# Industrial-Controller_ESP8266.net
KiCad netlist of a schematic drawn in Altium Designer
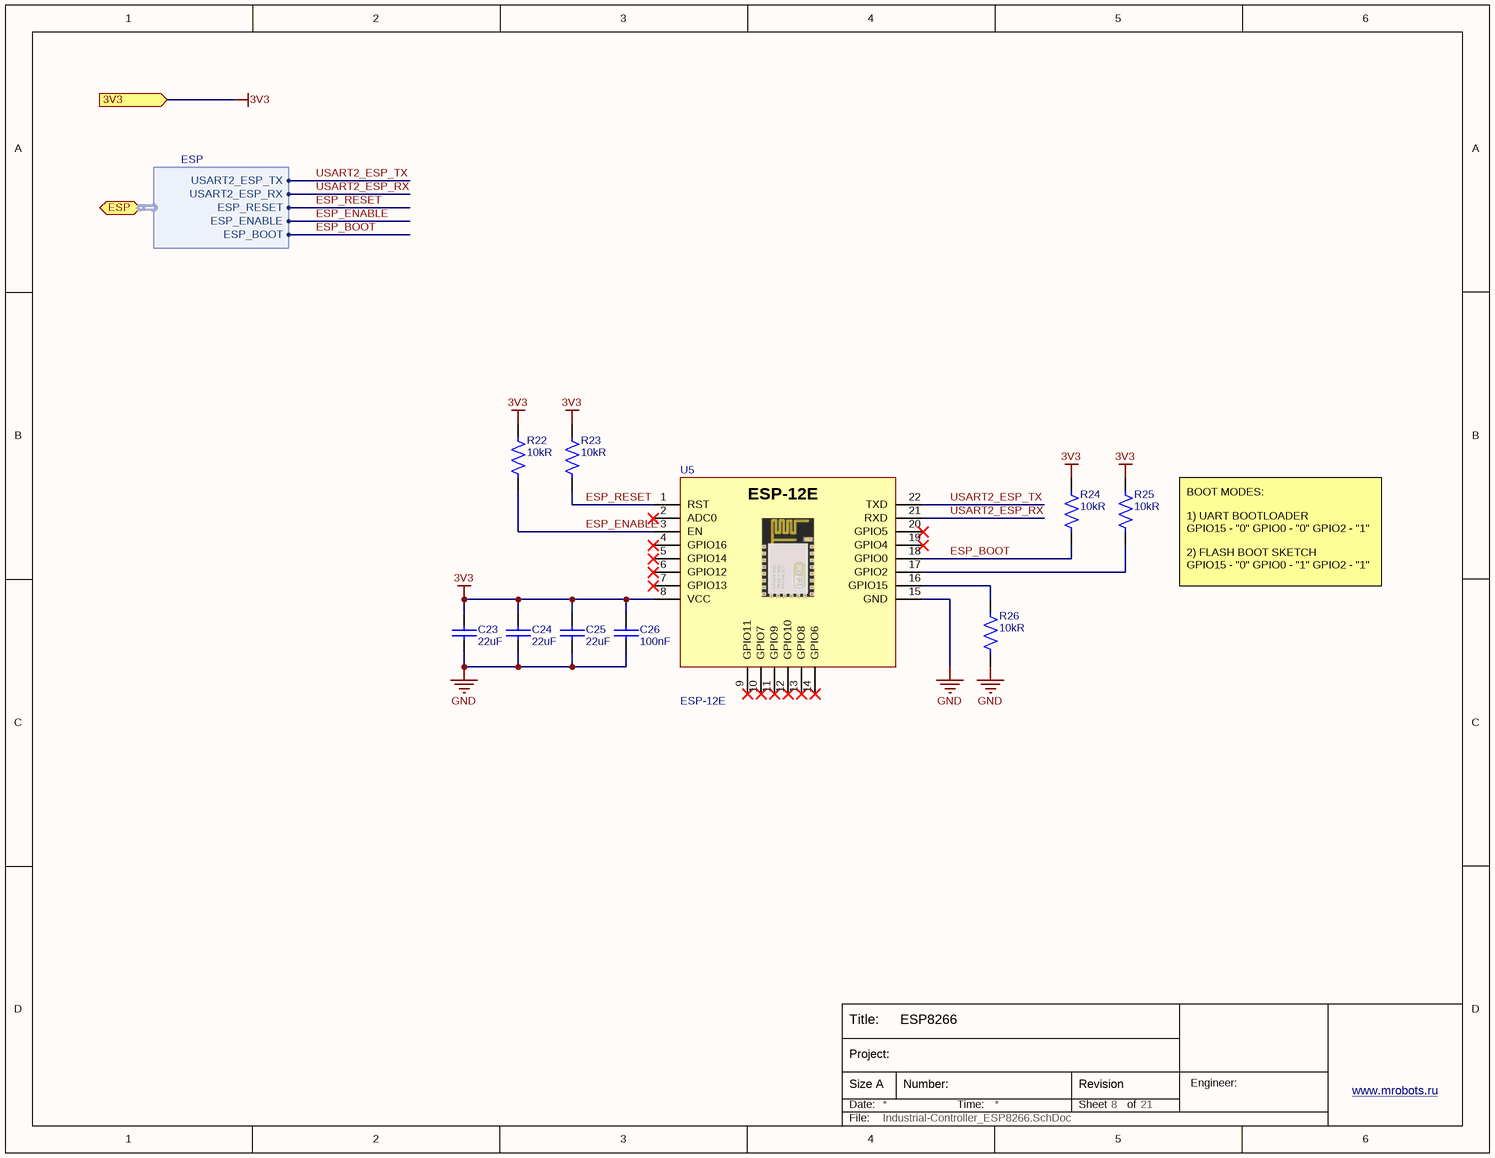
[diagram p0: Industrial-Controller_ESP8266.SchDoc]

(export (version "E")
  (design (tool "Eeschema 10.0.6"))
  (components
    (comp (ref "C23")
      (value "22uF")
      (footprint "CAP_1210")
      (description "CAP CER 22UF 25V X7R 1210")
      (fields (field (name "TOLERANCE") "10%"))
      (libsource (lib "Industrial-Controller") (part "CL32B226KAJNNNE"))
    )
    (comp (ref "C24")
      (value "22uF")
      (footprint "CAP_1210")
      (description "CAP CER 22UF 25V X7R 1210")
      (fields (field (name "TOLERANCE") "10%"))
      (libsource (lib "Industrial-Controller") (part "CL32B226KAJNNNE"))
    )
    (comp (ref "C25")
      (value "22uF")
      (footprint "CAP_1210")
      (description "CAP CER 22UF 25V X7R 1210")
      (fields (field (name "TOLERANCE") "10%"))
      (libsource (lib "Industrial-Controller") (part "CL32B226KAJNNNE"))
    )
    (comp (ref "C26")
      (value "100nF")
      (footprint "CAP_0603")
      (description "CAP CER 0.1UF 50V X7R 0603")
      (fields (field (name "TOLERANCE") "10%"))
      (libsource (lib "Industrial-Controller") (part "CL10B104KB8NNNL"))
    )
    (comp (ref "R22")
      (value "10kR")
      (footprint "RES_0603")
      (description "RES 10K OHM 1% 1/10W 0603")
      (fields (field (name "TOLERANCE") "1%"))
      (libsource (lib "Industrial-Controller") (part "RC0603FR-0710KL"))
    )
    (comp (ref "R23")
      (value "10kR")
      (footprint "RES_0603")
      (description "RES 10K OHM 1% 1/10W 0603")
      (fields (field (name "TOLERANCE") "1%"))
      (libsource (lib "Industrial-Controller") (part "RC0603FR-0710KL"))
    )
    (comp (ref "R24")
      (value "10kR")
      (footprint "RES_0603")
      (description "RES 10K OHM 1% 1/10W 0603")
      (fields (field (name "TOLERANCE") "1%"))
      (libsource (lib "Industrial-Controller") (part "RC0603FR-0710KL"))
    )
    (comp (ref "R25")
      (value "10kR")
      (footprint "RES_0603")
      (description "RES 10K OHM 1% 1/10W 0603")
      (fields (field (name "TOLERANCE") "1%"))
      (libsource (lib "Industrial-Controller") (part "RC0603FR-0710KL"))
    )
    (comp (ref "R26")
      (value "10kR")
      (footprint "RES_0603")
      (description "RES 10K OHM 1% 1/10W 0603")
      (fields (field (name "TOLERANCE") "1%"))
      (libsource (lib "Industrial-Controller") (part "RC0603FR-0710KL"))
    )
    (comp (ref "U5")
      (value "ESP-12E")
      (footprint "ESP-12E")
      (description "MOD 802.11 BLUETOOTH 5 CHIP ANT")
      (libsource (lib "Industrial-Controller") (part "ESP-12E"))
    )
  )
  (nets
    (net (code "2") (name "/ESP_BOOT") (class "Default")
      (node (ref "R24") (pin "2") (pinfunction "2_2") (pintype "passive"))
      (node (ref "U5") (pin "18") (pinfunction "GPIO0_18") (pintype "passive"))
    )
    (net (code "3") (name "/ESP_ENABLE") (class "Default")
      (node (ref "R22") (pin "2") (pinfunction "2_2") (pintype "passive"))
      (node (ref "U5") (pin "3") (pinfunction "EN_3") (pintype "passive"))
    )
    (net (code "4") (name "/ESP_RESET") (class "Default")
      (node (ref "R23") (pin "2") (pinfunction "2_2") (pintype "passive"))
      (node (ref "U5") (pin "1") (pinfunction "RST_1") (pintype "passive"))
    )
    (net (code "5") (name "/USART2_ESP_RX") (class "Default")
      (node (ref "U5") (pin "21") (pinfunction "RXD_21") (pintype "passive"))
    )
    (net (code "6") (name "/USART2_ESP_TX") (class "Default")
      (node (ref "U5") (pin "22") (pinfunction "TXD_22") (pintype "passive"))
    )
    (net (code "8") (name "3V3") (class "Default")
      (node (ref "C23") (pin "2") (pinfunction "2_2") (pintype "passive"))
      (node (ref "C24") (pin "2") (pinfunction "2_2") (pintype "passive"))
      (node (ref "C25") (pin "2") (pinfunction "2_2") (pintype "passive"))
      (node (ref "C26") (pin "1") (pinfunction "1_1") (pintype "passive"))
      (node (ref "R22") (pin "1") (pinfunction "1_1") (pintype "passive"))
      (node (ref "R23") (pin "1") (pinfunction "1_1") (pintype "passive"))
      (node (ref "R24") (pin "1") (pinfunction "1_1") (pintype "passive"))
      (node (ref "R25") (pin "1") (pinfunction "1_1") (pintype "passive"))
      (node (ref "U5") (pin "8") (pinfunction "VCC_8") (pintype "passive"))
    )
    (net (code "9") (name "GND") (class "Default")
      (node (ref "C23") (pin "1") (pinfunction "1_1") (pintype "passive"))
      (node (ref "C24") (pin "1") (pinfunction "1_1") (pintype "passive"))
      (node (ref "C25") (pin "1") (pinfunction "1_1") (pintype "passive"))
      (node (ref "C26") (pin "2") (pinfunction "2_2") (pintype "passive"))
      (node (ref "R26") (pin "2") (pinfunction "2_2") (pintype "passive"))
      (node (ref "U5") (pin "15") (pinfunction "GND_15") (pintype "passive"))
    )
    (net (code "10") (name "Net-(U5-GPIO2)") (class "Default")
      (node (ref "R25") (pin "2") (pinfunction "2_2") (pintype "passive"))
      (node (ref "U5") (pin "17") (pinfunction "GPIO2_17") (pintype "passive"))
    )
    (net (code "11") (name "Net-(U5-GPIO15)") (class "Default")
      (node (ref "R26") (pin "1") (pinfunction "1_1") (pintype "passive"))
      (node (ref "U5") (pin "16") (pinfunction "GPIO15_16") (pintype "passive"))
    )
    (net (code "12") (name "unconnected-(U5-ADC0-Pad2)") (class "Default")
      (node (ref "U5") (pin "2") (pinfunction "ADC0_2") (pintype "passive+no_connect"))
    )
    (net (code "13") (name "unconnected-(U5-GPIO4-Pad19)") (class "Default")
      (node (ref "U5") (pin "19") (pinfunction "GPIO4_19") (pintype "passive+no_connect"))
    )
    (net (code "14") (name "unconnected-(U5-GPIO5-Pad20)") (class "Default")
      (node (ref "U5") (pin "20") (pinfunction "GPIO5_20") (pintype "passive+no_connect"))
    )
    (net (code "15") (name "unconnected-(U5-GPIO6-Pad14)") (class "Default")
      (node (ref "U5") (pin "14") (pinfunction "GPIO6_14") (pintype "passive+no_connect"))
    )
    (net (code "16") (name "unconnected-(U5-GPIO7-Pad10)") (class "Default")
      (node (ref "U5") (pin "10") (pinfunction "GPIO7_10") (pintype "passive+no_connect"))
    )
    (net (code "17") (name "unconnected-(U5-GPIO8-Pad13)") (class "Default")
      (node (ref "U5") (pin "13") (pinfunction "GPIO8_13") (pintype "passive+no_connect"))
    )
    (net (code "18") (name "unconnected-(U5-GPIO9-Pad11)") (class "Default")
      (node (ref "U5") (pin "11") (pinfunction "GPIO9_11") (pintype "passive+no_connect"))
    )
    (net (code "19") (name "unconnected-(U5-GPIO10-Pad12)") (class "Default")
      (node (ref "U5") (pin "12") (pinfunction "GPIO10_12") (pintype "passive+no_connect"))
    )
    (net (code "20") (name "unconnected-(U5-GPIO11-Pad9)") (class "Default")
      (node (ref "U5") (pin "9") (pinfunction "GPIO11_9") (pintype "passive+no_connect"))
    )
    (net (code "21") (name "unconnected-(U5-GPIO12-Pad6)") (class "Default")
      (node (ref "U5") (pin "6") (pinfunction "GPIO12_6") (pintype "passive+no_connect"))
    )
    (net (code "22") (name "unconnected-(U5-GPIO13-Pad7)") (class "Default")
      (node (ref "U5") (pin "7") (pinfunction "GPIO13_7") (pintype "passive+no_connect"))
    )
    (net (code "23") (name "unconnected-(U5-GPIO14-Pad5)") (class "Default")
      (node (ref "U5") (pin "5") (pinfunction "GPIO14_5") (pintype "passive+no_connect"))
    )
    (net (code "24") (name "unconnected-(U5-GPIO16-Pad4)") (class "Default")
      (node (ref "U5") (pin "4") (pinfunction "GPIO16_4") (pintype "passive+no_connect"))
    )
  )
)
